# resistor_test.net
KiCad netlist of a schematic drawn in EAGLE
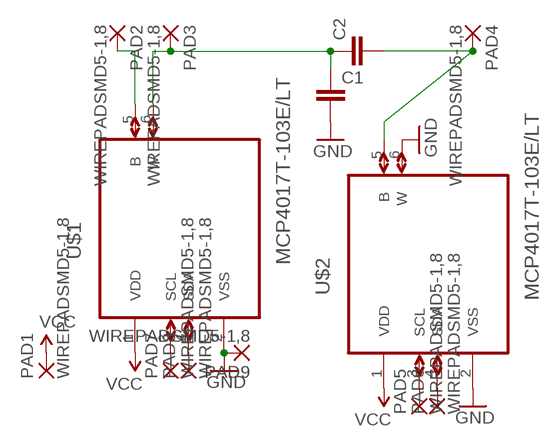
[diagram p0: schematic, sheet 1]

(export (version "E")
  (design (tool "Eeschema 10.0.6"))
  (components
    (comp (ref "C1")
      (value "C-EUC0603")
      (footprint "eagle-import:C0603")
      (libsource (lib "eagle-import") (part "C-EUC0603"))
    )
    (comp (ref "C2")
      (value "C-EUC0603")
      (footprint "eagle-import:C0603")
      (libsource (lib "eagle-import") (part "C-EUC0603"))
    )
    (comp (ref "PAD1")
      (value "WIREPADSMD5-1,8")
      (footprint "eagle-import:5-1,8")
      (libsource (lib "eagle-import") (part "WIREPADSMD5-1,8"))
    )
    (comp (ref "PAD2")
      (value "WIREPADSMD5-1,8")
      (footprint "eagle-import:5-1,8")
      (libsource (lib "eagle-import") (part "WIREPADSMD5-1,8"))
    )
    (comp (ref "PAD3")
      (value "WIREPADSMD5-1,8")
      (footprint "eagle-import:5-1,8")
      (libsource (lib "eagle-import") (part "WIREPADSMD5-1,8"))
    )
    (comp (ref "PAD4")
      (value "WIREPADSMD5-1,8")
      (footprint "eagle-import:5-1,8")
      (libsource (lib "eagle-import") (part "WIREPADSMD5-1,8"))
    )
    (comp (ref "PAD5")
      (value "WIREPADSMD5-1,8")
      (footprint "eagle-import:5-1,8")
      (libsource (lib "eagle-import") (part "WIREPADSMD5-1,8"))
    )
    (comp (ref "PAD6")
      (value "WIREPADSMD5-1,8")
      (footprint "eagle-import:5-1,8")
      (libsource (lib "eagle-import") (part "WIREPADSMD5-1,8"))
    )
    (comp (ref "PAD7")
      (value "WIREPADSMD5-1,8")
      (footprint "eagle-import:5-1,8")
      (libsource (lib "eagle-import") (part "WIREPADSMD5-1,8"))
    )
    (comp (ref "PAD8")
      (value "WIREPADSMD5-1,8")
      (footprint "eagle-import:5-1,8")
      (libsource (lib "eagle-import") (part "WIREPADSMD5-1,8"))
    )
    (comp (ref "PAD9")
      (value "WIREPADSMD5-1,8")
      (footprint "eagle-import:5-1,8")
      (libsource (lib "eagle-import") (part "WIREPADSMD5-1,8"))
    )
    (comp (ref "U$1")
      (value "MCP4017T-103E/LT")
      (footprint "eagle-import:SOT65P210X110-6N")
      (fields (field (name "MF") "Microchip"))
      (libsource (lib "eagle-import") (part "MCP4017T-103E/LT"))
    )
    (comp (ref "U$2")
      (value "MCP4017T-103E/LT")
      (footprint "eagle-import:SOT65P210X110-6N")
      (fields (field (name "MF") "Microchip"))
      (libsource (lib "eagle-import") (part "MCP4017T-103E/LT"))
    )
  )
  (nets
    (net (code "1") (name "GND") (class "Default")
      (node (ref "C1") (pin "2") (pinfunction "2_2") (pintype "passive"))
      (node (ref "PAD9") (pin "1") (pinfunction "P_1") (pintype "passive"))
      (node (ref "U$1") (pin "2") (pinfunction "VSS_2") (pintype "power_in"))
      (node (ref "U$2") (pin "2") (pinfunction "VSS_2") (pintype "power_in"))
      (node (ref "U$2") (pin "6") (pinfunction "W_6") (pintype "bidirectional"))
    )
    (net (code "2") (name "Net-(PAD2-P)") (class "Default")
      (node (ref "PAD2") (pin "1") (pinfunction "P_1") (pintype "passive"))
      (node (ref "U$1") (pin "5") (pinfunction "B_5") (pintype "bidirectional"))
    )
    (net (code "3") (name "Net-(PAD3-P)") (class "Default")
      (node (ref "C1") (pin "1") (pinfunction "1_1") (pintype "passive"))
      (node (ref "C2") (pin "1") (pinfunction "1_1") (pintype "passive"))
      (node (ref "PAD3") (pin "1") (pinfunction "P_1") (pintype "passive"))
      (node (ref "U$1") (pin "6") (pinfunction "W_6") (pintype "bidirectional"))
    )
    (net (code "4") (name "Net-(PAD4-P)") (class "Default")
      (node (ref "C2") (pin "2") (pinfunction "2_2") (pintype "passive"))
      (node (ref "PAD4") (pin "1") (pinfunction "P_1") (pintype "passive"))
      (node (ref "U$2") (pin "5") (pinfunction "B_5") (pintype "bidirectional"))
    )
    (net (code "5") (name "Net-(PAD5-P)") (class "Default")
      (node (ref "PAD5") (pin "1") (pinfunction "P_1") (pintype "passive"))
      (node (ref "U$2") (pin "3") (pinfunction "SCL_3") (pintype "bidirectional"))
    )
    (net (code "6") (name "Net-(PAD6-P)") (class "Default")
      (node (ref "PAD6") (pin "1") (pinfunction "P_1") (pintype "passive"))
      (node (ref "U$2") (pin "4") (pinfunction "SDA_4") (pintype "bidirectional"))
    )
    (net (code "7") (name "Net-(PAD7-P)") (class "Default")
      (node (ref "PAD7") (pin "1") (pinfunction "P_1") (pintype "passive"))
      (node (ref "U$1") (pin "3") (pinfunction "SCL_3") (pintype "bidirectional"))
    )
    (net (code "8") (name "Net-(PAD8-P)") (class "Default")
      (node (ref "PAD8") (pin "1") (pinfunction "P_1") (pintype "passive"))
      (node (ref "U$1") (pin "4") (pinfunction "SDA_4") (pintype "bidirectional"))
    )
    (net (code "9") (name "VCC") (class "Default")
      (node (ref "PAD1") (pin "1") (pinfunction "P_1") (pintype "passive"))
      (node (ref "U$1") (pin "1") (pinfunction "VDD_1") (pintype "power_in"))
      (node (ref "U$2") (pin "1") (pinfunction "VDD_1") (pintype "power_in"))
    )
  )
)
